# SUSTAINA-PMX-Control-Board.net
KiCad netlist of a schematic drawn in EAGLE
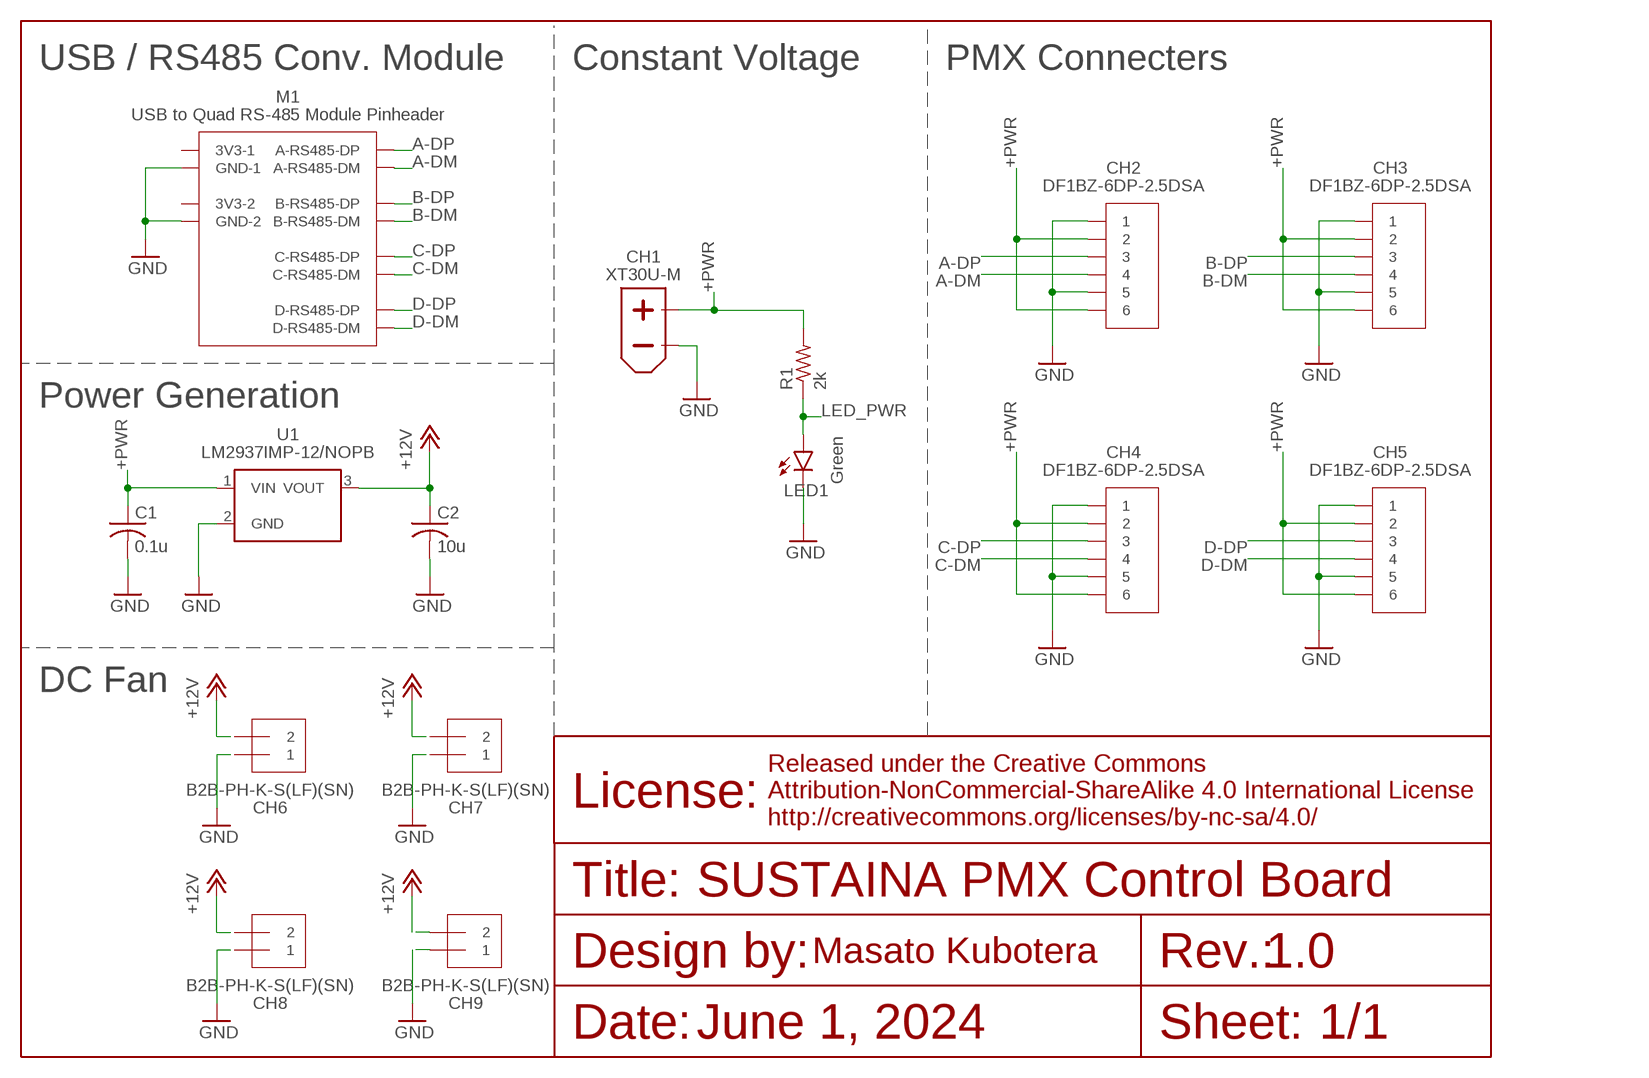
[diagram p0: schematic, sheet 1]

(export (version "E")
  (design (tool "Eeschema 10.0.6"))
  (components
    (comp (ref "C1")
      (value "0.1u")
      (footprint "eagle-import:C0603")
      (libsource (lib "eagle-import") (part "C-USC0603"))
    )
    (comp (ref "C2")
      (value "10u")
      (footprint "eagle-import:C0603")
      (libsource (lib "eagle-import") (part "C-USC0603"))
    )
    (comp (ref "CH1")
      (value "XT30U-M")
      (footprint "eagle-import:XT30U-M")
      (libsource (lib "eagle-import") (part "XT30U-M"))
    )
    (comp (ref "CH2")
      (value "DF1BZ-6DP-25DSA")
      (footprint "eagle-import:DF1BZ-6DP-25DSA")
      (libsource (lib "eagle-import") (part "DF1BZ-6DP-25DSA"))
    )
    (comp (ref "CH3")
      (value "DF1BZ-6DP-25DSA")
      (footprint "eagle-import:DF1BZ-6DP-25DSA")
      (libsource (lib "eagle-import") (part "DF1BZ-6DP-25DSA"))
    )
    (comp (ref "CH4")
      (value "DF1BZ-6DP-25DSA")
      (footprint "eagle-import:DF1BZ-6DP-25DSA")
      (libsource (lib "eagle-import") (part "DF1BZ-6DP-25DSA"))
    )
    (comp (ref "CH5")
      (value "DF1BZ-6DP-25DSA")
      (footprint "eagle-import:DF1BZ-6DP-25DSA")
      (libsource (lib "eagle-import") (part "DF1BZ-6DP-25DSA"))
    )
    (comp (ref "CH6")
      (value "B2B-PH-K-S(LF)(SN)")
      (footprint "eagle-import:B2B-PH-K-S(LF)(SN)")
      (libsource (lib "eagle-import") (part "B2B-PH-K-S(LF)(SN)"))
    )
    (comp (ref "CH7")
      (value "B2B-PH-K-S(LF)(SN)")
      (footprint "eagle-import:B2B-PH-K-S(LF)(SN)")
      (libsource (lib "eagle-import") (part "B2B-PH-K-S(LF)(SN)"))
    )
    (comp (ref "CH8")
      (value "B2B-PH-K-S(LF)(SN)")
      (footprint "eagle-import:B2B-PH-K-S(LF)(SN)")
      (libsource (lib "eagle-import") (part "B2B-PH-K-S(LF)(SN)"))
    )
    (comp (ref "CH9")
      (value "B2B-PH-K-S(LF)(SN)")
      (footprint "eagle-import:B2B-PH-K-S(LF)(SN)")
      (libsource (lib "eagle-import") (part "B2B-PH-K-S(LF)(SN)"))
    )
    (comp (ref "LED1")
      (value "Green")
      (footprint "eagle-import:SML0603")
      (libsource (lib "eagle-import") (part "LEDSML0603"))
    )
    (comp (ref "M1")
      (value "USB-TO-QUAD-RS-485-CONV-MODULESINGLE")
      (footprint "eagle-import:USB-TO-QUAD-RS-485-CONV-MODULE-TPLACE-SINGLE")
      (libsource (lib "eagle-import") (part "USB-TO-QUAD-RS-485-CONV-MODULESINGLE"))
    )
    (comp (ref "R1")
      (value "2k")
      (footprint "eagle-import:R0603")
      (libsource (lib "eagle-import") (part "R-US_R0603"))
    )
    (comp (ref "U1")
      (value "LM2937IMP-12NOPB")
      (footprint "eagle-import:SOT-223")
      (libsource (lib "eagle-import") (part "LM2937IMP-12NOPB"))
    )
  )
  (nets
    (net (code "1") (name "+12V") (class "Default")
      (node (ref "C2") (pin "1") (pinfunction "1_1") (pintype "passive"))
      (node (ref "CH6") (pin "2") (pinfunction "2_2") (pintype "bidirectional"))
      (node (ref "CH7") (pin "2") (pinfunction "2_2") (pintype "bidirectional"))
      (node (ref "CH8") (pin "2") (pinfunction "2_2") (pintype "bidirectional"))
      (node (ref "CH9") (pin "2") (pinfunction "2_2") (pintype "bidirectional"))
      (node (ref "U1") (pin "3") (pinfunction "VOUT_3") (pintype "bidirectional"))
    )
    (net (code "2") (name "/+PWR") (class "Default")
      (node (ref "C1") (pin "1") (pinfunction "1_1") (pintype "passive"))
      (node (ref "CH1") (pin "+") (pinfunction "+_+") (pintype "power_in"))
      (node (ref "CH2") (pin "2") (pinfunction "2_2") (pintype "bidirectional"))
      (node (ref "CH2") (pin "6") (pinfunction "6_6") (pintype "bidirectional"))
      (node (ref "CH3") (pin "2") (pinfunction "2_2") (pintype "bidirectional"))
      (node (ref "CH3") (pin "6") (pinfunction "6_6") (pintype "bidirectional"))
      (node (ref "CH4") (pin "2") (pinfunction "2_2") (pintype "bidirectional"))
      (node (ref "CH4") (pin "6") (pinfunction "6_6") (pintype "bidirectional"))
      (node (ref "CH5") (pin "2") (pinfunction "2_2") (pintype "bidirectional"))
      (node (ref "CH5") (pin "6") (pinfunction "6_6") (pintype "bidirectional"))
      (node (ref "R1") (pin "2") (pinfunction "2_2") (pintype "passive"))
      (node (ref "U1") (pin "1") (pinfunction "VIN_1") (pintype "bidirectional"))
    )
    (net (code "3") (name "/A-DM") (class "Default")
      (node (ref "CH2") (pin "4") (pinfunction "4_4") (pintype "bidirectional"))
      (node (ref "M1") (pin "A-RS-485-DM1") (pinfunction "A-RS485-DM_A-RS-485-DM1") (pintype "bidirectional"))
    )
    (net (code "4") (name "/A-DP") (class "Default")
      (node (ref "CH2") (pin "3") (pinfunction "3_3") (pintype "bidirectional"))
      (node (ref "M1") (pin "A-RS-485-DP1") (pinfunction "A-RS485-DP_A-RS-485-DP1") (pintype "bidirectional"))
    )
    (net (code "5") (name "/B-DM") (class "Default")
      (node (ref "CH3") (pin "4") (pinfunction "4_4") (pintype "bidirectional"))
      (node (ref "M1") (pin "B-RS-485-DM1") (pinfunction "B-RS485-DM_B-RS-485-DM1") (pintype "bidirectional"))
    )
    (net (code "6") (name "/B-DP") (class "Default")
      (node (ref "CH3") (pin "3") (pinfunction "3_3") (pintype "bidirectional"))
      (node (ref "M1") (pin "B-RS-485-DP1") (pinfunction "B-RS485-DP_B-RS-485-DP1") (pintype "bidirectional"))
    )
    (net (code "7") (name "/C-DM") (class "Default")
      (node (ref "CH4") (pin "4") (pinfunction "4_4") (pintype "bidirectional"))
      (node (ref "M1") (pin "C-RS-485-DM1") (pinfunction "C-RS485-DM_C-RS-485-DM1") (pintype "bidirectional"))
    )
    (net (code "8") (name "/C-DP") (class "Default")
      (node (ref "CH4") (pin "3") (pinfunction "3_3") (pintype "bidirectional"))
      (node (ref "M1") (pin "C-RS-485-DP1") (pinfunction "C-RS485-DP_C-RS-485-DP1") (pintype "bidirectional"))
    )
    (net (code "9") (name "/D-DM") (class "Default")
      (node (ref "CH5") (pin "4") (pinfunction "4_4") (pintype "bidirectional"))
      (node (ref "M1") (pin "D-RS-485-DM1") (pinfunction "D-RS485-DM_D-RS-485-DM1") (pintype "bidirectional"))
    )
    (net (code "10") (name "/D-DP") (class "Default")
      (node (ref "CH5") (pin "3") (pinfunction "3_3") (pintype "bidirectional"))
      (node (ref "M1") (pin "D-RS-485-DP1") (pinfunction "D-RS485-DP_D-RS-485-DP1") (pintype "bidirectional"))
    )
    (net (code "11") (name "/LED_PWR") (class "Default")
      (node (ref "LED1") (pin "A") (pinfunction "A_A") (pintype "passive"))
      (node (ref "R1") (pin "1") (pinfunction "1_1") (pintype "passive"))
    )
    (net (code "12") (name "GND") (class "Default")
      (node (ref "C1") (pin "2") (pinfunction "2_2") (pintype "passive"))
      (node (ref "C2") (pin "2") (pinfunction "2_2") (pintype "passive"))
      (node (ref "CH1") (pin "-") (pinfunction "-_-") (pintype "power_in"))
      (node (ref "CH2") (pin "1") (pinfunction "1_1") (pintype "bidirectional"))
      (node (ref "CH2") (pin "5") (pinfunction "5_5") (pintype "bidirectional"))
      (node (ref "CH3") (pin "1") (pinfunction "1_1") (pintype "bidirectional"))
      (node (ref "CH3") (pin "5") (pinfunction "5_5") (pintype "bidirectional"))
      (node (ref "CH4") (pin "1") (pinfunction "1_1") (pintype "bidirectional"))
      (node (ref "CH4") (pin "5") (pinfunction "5_5") (pintype "bidirectional"))
      (node (ref "CH5") (pin "1") (pinfunction "1_1") (pintype "bidirectional"))
      (node (ref "CH5") (pin "5") (pinfunction "5_5") (pintype "bidirectional"))
      (node (ref "CH6") (pin "1") (pinfunction "1_1") (pintype "bidirectional"))
      (node (ref "CH7") (pin "1") (pinfunction "1_1") (pintype "bidirectional"))
      (node (ref "CH8") (pin "1") (pinfunction "1_1") (pintype "bidirectional"))
      (node (ref "CH9") (pin "1") (pinfunction "1_1") (pintype "bidirectional"))
      (node (ref "LED1") (pin "C") (pinfunction "C_C") (pintype "passive"))
      (node (ref "M1") (pin "GND-1") (pinfunction "GND-1_GND-1") (pintype "bidirectional"))
      (node (ref "M1") (pin "GND-2") (pinfunction "GND-2_GND-2") (pintype "bidirectional"))
      (node (ref "U1") (pin "2") (pinfunction "GND_2") (pintype "bidirectional"))
    )
    (net (code "13") (name "unconnected-(M1-Pad3V3-1)") (class "Default")
      (node (ref "M1") (pin "3V3-1") (pinfunction "3V3-1_3V3-1") (pintype "bidirectional"))
    )
    (net (code "14") (name "unconnected-(M1-Pad3V3-2)") (class "Default")
      (node (ref "M1") (pin "3V3-2") (pinfunction "3V3-2_3V3-2") (pintype "bidirectional"))
    )
  )
)
